# item_2022_Frontend_01.net
KiCad netlist of a schematic drawn in EAGLE
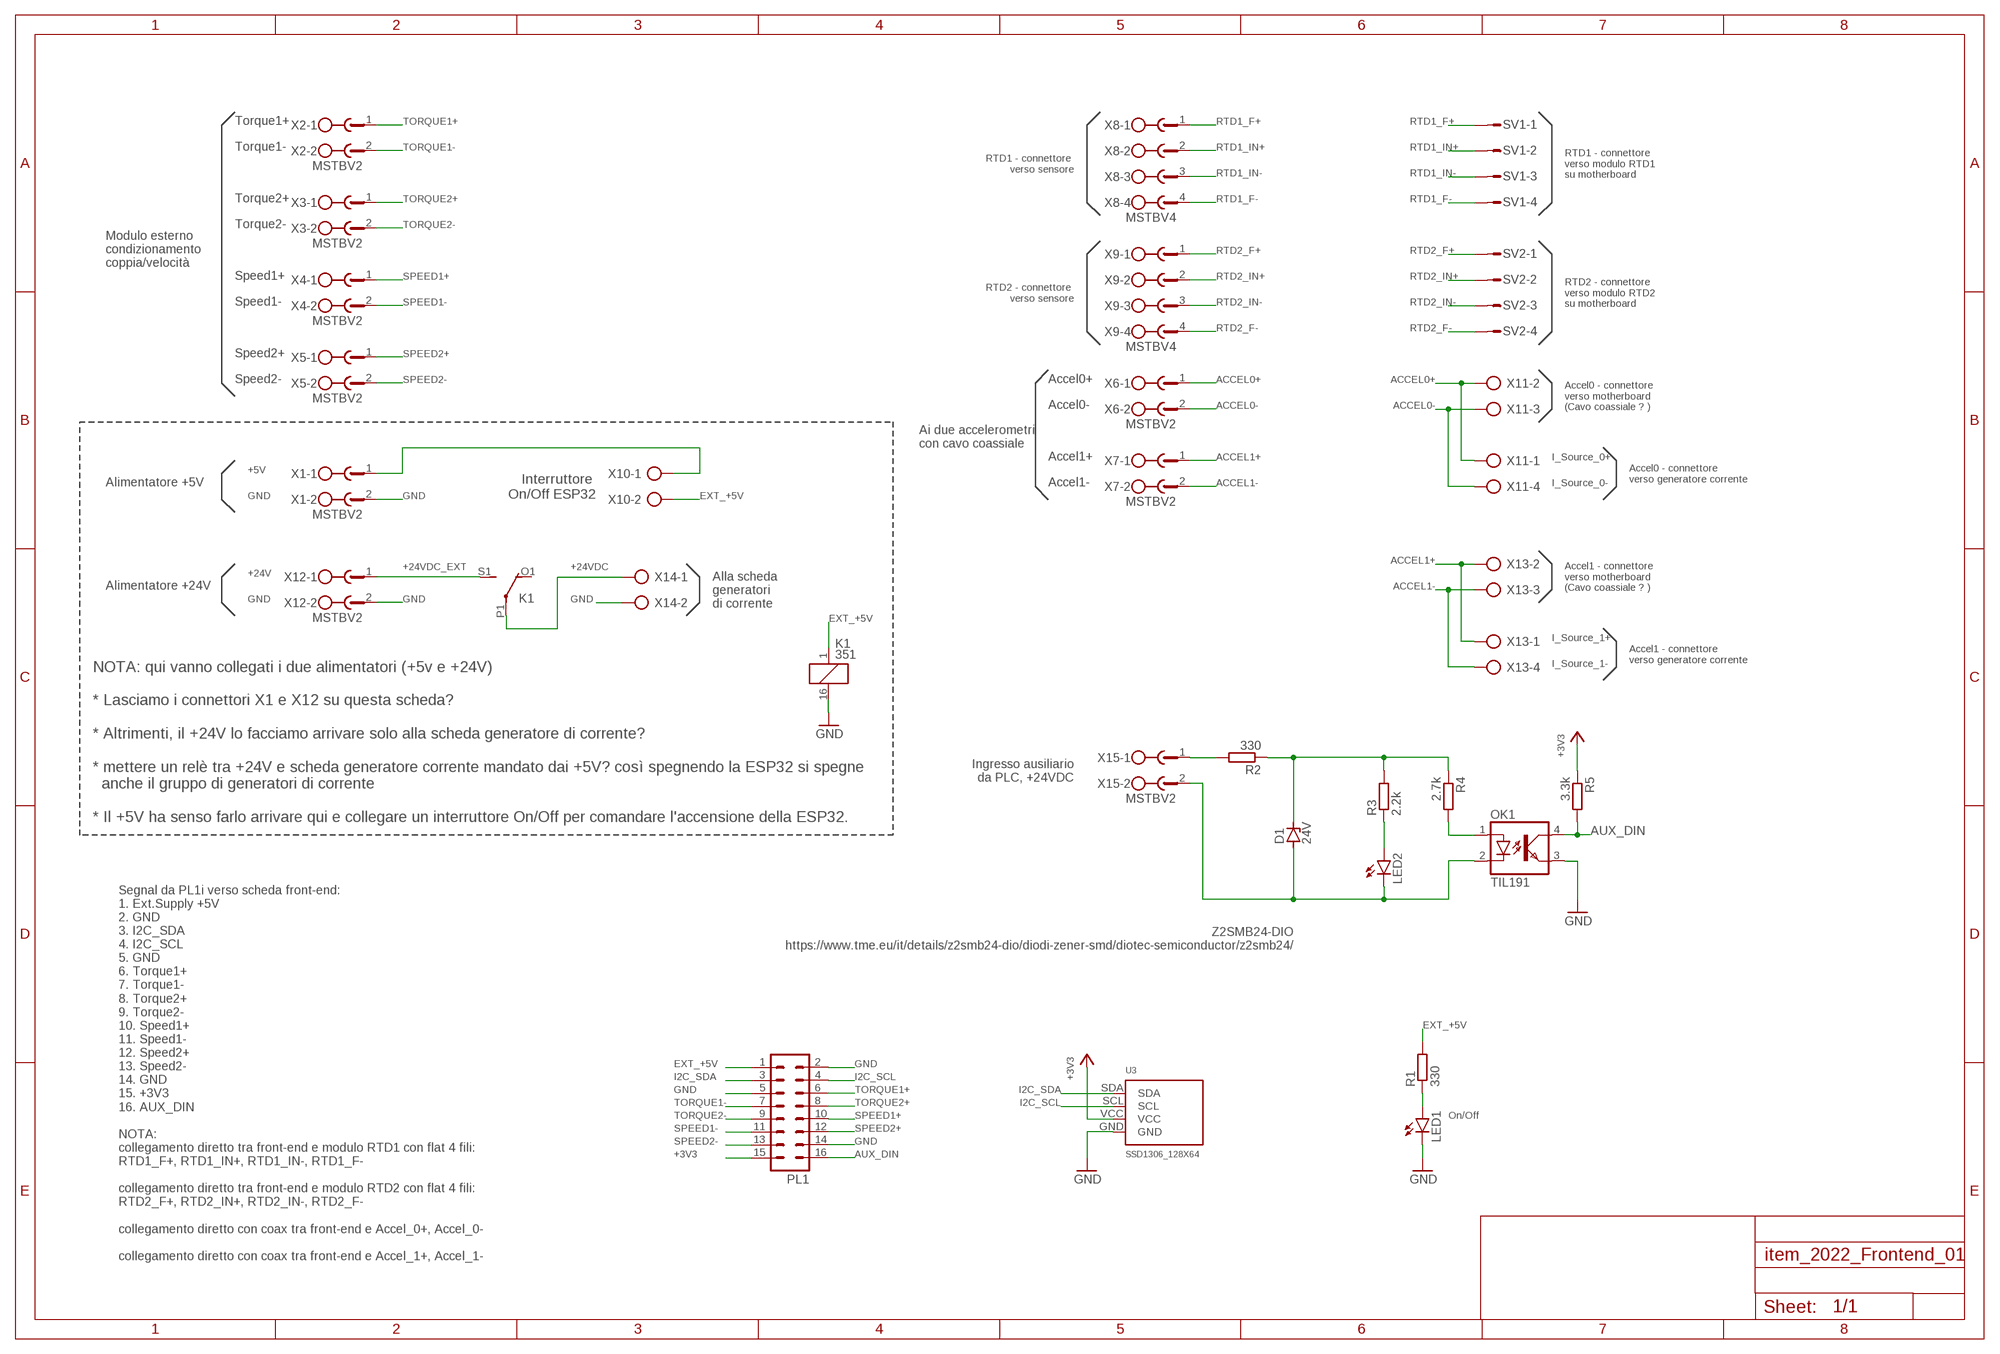
[diagram p0: schematic, sheet 1]

(export (version "E")
  (design (tool "Eeschema 10.0.6"))
  (components
    (comp (ref "D1")
      (value "24V")
      (footprint "eagle-import:SMB")
      (libsource (lib "eagle-import") (part "ZENER-DIODESMB"))
    )
    (comp (ref "K1")
      (value "351")
      (footprint "eagle-import:351")
      (libsource (lib "eagle-import") (part "351"))
    )
    (comp (ref "LED1")
      (value "LED5MM")
      (footprint "eagle-import:LED5MM")
      (libsource (lib "eagle-import") (part "LED5MM"))
    )
    (comp (ref "LED2")
      (value "LED5MM")
      (footprint "eagle-import:LED5MM")
      (libsource (lib "eagle-import") (part "LED5MM"))
    )
    (comp (ref "OK1")
      (value "TIL191")
      (footprint "eagle-import:DIL04")
      (libsource (lib "eagle-import") (part "TIL191"))
    )
    (comp (ref "PL1")
      (value "16V")
      (footprint "eagle-import:16V")
      (libsource (lib "eagle-import") (part "16V"))
    )
    (comp (ref "R1")
      (value "330")
      (footprint "eagle-import:R0805")
      (libsource (lib "eagle-import") (part "R-EU_R0805"))
    )
    (comp (ref "R2")
      (value "330")
      (footprint "eagle-import:R0805")
      (libsource (lib "eagle-import") (part "R-EU_R0805"))
    )
    (comp (ref "R3")
      (value "2.2k")
      (footprint "eagle-import:R0805")
      (libsource (lib "eagle-import") (part "R-EU_R0805"))
    )
    (comp (ref "R4")
      (value "2.7k")
      (footprint "eagle-import:R0805")
      (libsource (lib "eagle-import") (part "R-EU_R0805"))
    )
    (comp (ref "R5")
      (value "3.3k")
      (footprint "eagle-import:R0805")
      (libsource (lib "eagle-import") (part "R-EU_R0805"))
    )
    (comp (ref "SV1")
      (value "S04P")
      (footprint "eagle-import:S04P")
      (libsource (lib "eagle-import") (part "S04P"))
    )
    (comp (ref "SV2")
      (value "S04P")
      (footprint "eagle-import:S04P")
      (libsource (lib "eagle-import") (part "S04P"))
    )
    (comp (ref "U3")
      (value "SSD1306_128X64")
      (footprint "eagle-import:128X64")
      (libsource (lib "eagle-import") (part "SSD1306_128X64"))
    )
    (comp (ref "X1")
      (value "MSTBV2")
      (footprint "eagle-import:MSTBV2")
      (fields (field (name "MPN") "MSTBV 2,5/2-GF-5.08"))
      (libsource (lib "eagle-import") (part "MSTBV2"))
    )
    (comp (ref "X2")
      (value "MSTBV2")
      (footprint "eagle-import:MSTBV2")
      (fields (field (name "MPN") "MSTBV 2,5/2-GF-5.08"))
      (libsource (lib "eagle-import") (part "MSTBV2"))
    )
    (comp (ref "X3")
      (value "MSTBV2")
      (footprint "eagle-import:MSTBV2")
      (fields (field (name "MPN") "MSTBV 2,5/2-GF-5.08"))
      (libsource (lib "eagle-import") (part "MSTBV2"))
    )
    (comp (ref "X4")
      (value "MSTBV2")
      (footprint "eagle-import:MSTBV2")
      (fields (field (name "MPN") "MSTBV 2,5/2-GF-5.08"))
      (libsource (lib "eagle-import") (part "MSTBV2"))
    )
    (comp (ref "X5")
      (value "MSTBV2")
      (footprint "eagle-import:MSTBV2")
      (fields (field (name "MPN") "MSTBV 2,5/2-GF-5.08"))
      (libsource (lib "eagle-import") (part "MSTBV2"))
    )
    (comp (ref "X6")
      (value "MSTBV2")
      (footprint "eagle-import:MSTBV2")
      (fields (field (name "MPN") "MSTBV 2,5/2-GF-5.08"))
      (libsource (lib "eagle-import") (part "MSTBV2"))
    )
    (comp (ref "X7")
      (value "MSTBV2")
      (footprint "eagle-import:MSTBV2")
      (fields (field (name "MPN") "MSTBV 2,5/2-GF-5.08"))
      (libsource (lib "eagle-import") (part "MSTBV2"))
    )
    (comp (ref "X8")
      (value "MSTBV4")
      (footprint "eagle-import:MSTBV4")
      (fields (field (name "MPN") "MSTBV 2,5/4-GF-5.08"))
      (libsource (lib "eagle-import") (part "MSTBV4"))
    )
    (comp (ref "X9")
      (value "MSTBV4")
      (footprint "eagle-import:MSTBV4")
      (fields (field (name "MPN") "MSTBV 2,5/4-GF-5.08"))
      (libsource (lib "eagle-import") (part "MSTBV4"))
    )
    (comp (ref "X10")
      (value "AK500/2")
      (footprint "eagle-import:AK500_2")
      (libsource (lib "eagle-import") (part "AK500/2"))
    )
    (comp (ref "X11")
      (value "AK500/4")
      (footprint "eagle-import:AK500_4")
      (libsource (lib "eagle-import") (part "AK500/4"))
    )
    (comp (ref "X12")
      (value "MSTBV2")
      (footprint "eagle-import:MSTBV2")
      (fields (field (name "MPN") "MSTBV 2,5/2-GF-5.08"))
      (libsource (lib "eagle-import") (part "MSTBV2"))
    )
    (comp (ref "X13")
      (value "AK500/4")
      (footprint "eagle-import:AK500_4")
      (libsource (lib "eagle-import") (part "AK500/4"))
    )
    (comp (ref "X14")
      (value "AK500/2")
      (footprint "eagle-import:AK500_2")
      (libsource (lib "eagle-import") (part "AK500/2"))
    )
    (comp (ref "X15")
      (value "MSTBV2")
      (footprint "eagle-import:MSTBV2")
      (fields (field (name "MPN") "MSTBV 2,5/2-GF-5.08"))
      (libsource (lib "eagle-import") (part "MSTBV2"))
    )
  )
  (nets
    (net (code "1") (name "+3V3") (class "Default")
      (node (ref "PL1") (pin "15") (pinfunction "15_15") (pintype "passive"))
      (node (ref "R5") (pin "1") (pinfunction "1_1") (pintype "passive"))
      (node (ref "U3") (pin "VCC") (pinfunction "VCC_VCC") (pintype "power_in"))
    )
    (net (code "2") (name "/+24VDC") (class "Default")
      (node (ref "K1") (pin "P1") (pinfunction "P_P1") (pintype "passive"))
      (node (ref "X14") (pin "1") (pinfunction "KL_1") (pintype "passive"))
    )
    (net (code "3") (name "/+24VDC_EXT") (class "Default")
      (node (ref "K1") (pin "S1") (pinfunction "S_S1") (pintype "passive"))
      (node (ref "X12") (pin "1") (pinfunction "1_1") (pintype "passive"))
    )
    (net (code "4") (name "/ACCEL0+") (class "Default")
      (node (ref "X11") (pin "1") (pinfunction "KL_1") (pintype "passive"))
      (node (ref "X11") (pin "2") (pinfunction "KL_2") (pintype "passive"))
      (node (ref "X6") (pin "1") (pinfunction "1_1") (pintype "passive"))
    )
    (net (code "5") (name "/ACCEL0-") (class "Default")
      (node (ref "X11") (pin "3") (pinfunction "KL_3") (pintype "passive"))
      (node (ref "X11") (pin "4") (pinfunction "KL_4") (pintype "passive"))
      (node (ref "X6") (pin "2") (pinfunction "1_2") (pintype "passive"))
    )
    (net (code "6") (name "/ACCEL1+") (class "Default")
      (node (ref "X13") (pin "1") (pinfunction "KL_1") (pintype "passive"))
      (node (ref "X13") (pin "2") (pinfunction "KL_2") (pintype "passive"))
      (node (ref "X7") (pin "1") (pinfunction "1_1") (pintype "passive"))
    )
    (net (code "7") (name "/ACCEL1-") (class "Default")
      (node (ref "X13") (pin "3") (pinfunction "KL_3") (pintype "passive"))
      (node (ref "X13") (pin "4") (pinfunction "KL_4") (pintype "passive"))
      (node (ref "X7") (pin "2") (pinfunction "1_2") (pintype "passive"))
    )
    (net (code "8") (name "/AUX_DIN") (class "Default")
      (node (ref "OK1") (pin "4") (pinfunction "COL_4") (pintype "passive"))
      (node (ref "PL1") (pin "16") (pinfunction "16_16") (pintype "passive"))
      (node (ref "R5") (pin "2") (pinfunction "2_2") (pintype "passive"))
    )
    (net (code "9") (name "/EXT_+5V") (class "Default")
      (node (ref "K1") (pin "1") (pinfunction "1_1") (pintype "passive"))
      (node (ref "PL1") (pin "1") (pinfunction "1_1") (pintype "passive"))
      (node (ref "R1") (pin "2") (pinfunction "2_2") (pintype "passive"))
      (node (ref "X10") (pin "2") (pinfunction "KL_2") (pintype "passive"))
    )
    (net (code "10") (name "/I2C_SCL") (class "Default")
      (node (ref "PL1") (pin "4") (pinfunction "4_4") (pintype "passive"))
      (node (ref "U3") (pin "SCL") (pinfunction "SCL_SCL") (pintype "bidirectional"))
    )
    (net (code "11") (name "/I2C_SDA") (class "Default")
      (node (ref "PL1") (pin "3") (pinfunction "3_3") (pintype "passive"))
      (node (ref "U3") (pin "SDA") (pinfunction "SDA_SDA") (pintype "bidirectional"))
    )
    (net (code "12") (name "/RTD1_F+") (class "Default")
      (node (ref "SV1") (pin "1") (pinfunction "S_1") (pintype "passive"))
      (node (ref "X8") (pin "1") (pinfunction "1_1") (pintype "passive"))
    )
    (net (code "13") (name "/RTD1_F-") (class "Default")
      (node (ref "SV1") (pin "4") (pinfunction "S_4") (pintype "passive"))
      (node (ref "X8") (pin "4") (pinfunction "1_4") (pintype "passive"))
    )
    (net (code "14") (name "/RTD1_IN+") (class "Default")
      (node (ref "SV1") (pin "2") (pinfunction "S_2") (pintype "passive"))
      (node (ref "X8") (pin "2") (pinfunction "1_2") (pintype "passive"))
    )
    (net (code "15") (name "/RTD1_IN-") (class "Default")
      (node (ref "SV1") (pin "3") (pinfunction "S_3") (pintype "passive"))
      (node (ref "X8") (pin "3") (pinfunction "1_3") (pintype "passive"))
    )
    (net (code "16") (name "/RTD2_F+") (class "Default")
      (node (ref "SV2") (pin "1") (pinfunction "S_1") (pintype "passive"))
      (node (ref "X9") (pin "1") (pinfunction "1_1") (pintype "passive"))
    )
    (net (code "17") (name "/RTD2_F-") (class "Default")
      (node (ref "SV2") (pin "4") (pinfunction "S_4") (pintype "passive"))
      (node (ref "X9") (pin "4") (pinfunction "1_4") (pintype "passive"))
    )
    (net (code "18") (name "/RTD2_IN+") (class "Default")
      (node (ref "SV2") (pin "2") (pinfunction "S_2") (pintype "passive"))
      (node (ref "X9") (pin "2") (pinfunction "1_2") (pintype "passive"))
    )
    (net (code "19") (name "/RTD2_IN-") (class "Default")
      (node (ref "SV2") (pin "3") (pinfunction "S_3") (pintype "passive"))
      (node (ref "X9") (pin "3") (pinfunction "1_3") (pintype "passive"))
    )
    (net (code "20") (name "/SPEED1+") (class "Default")
      (node (ref "PL1") (pin "10") (pinfunction "10_10") (pintype "passive"))
      (node (ref "X4") (pin "1") (pinfunction "1_1") (pintype "passive"))
    )
    (net (code "21") (name "/SPEED1-") (class "Default")
      (node (ref "PL1") (pin "11") (pinfunction "11_11") (pintype "passive"))
      (node (ref "X4") (pin "2") (pinfunction "1_2") (pintype "passive"))
    )
    (net (code "22") (name "/SPEED2+") (class "Default")
      (node (ref "PL1") (pin "12") (pinfunction "12_12") (pintype "passive"))
      (node (ref "X5") (pin "1") (pinfunction "1_1") (pintype "passive"))
    )
    (net (code "23") (name "/SPEED2-") (class "Default")
      (node (ref "PL1") (pin "13") (pinfunction "13_13") (pintype "passive"))
      (node (ref "X5") (pin "2") (pinfunction "1_2") (pintype "passive"))
    )
    (net (code "24") (name "/TORQUE1+") (class "Default")
      (node (ref "PL1") (pin "6") (pinfunction "6_6") (pintype "passive"))
      (node (ref "X2") (pin "1") (pinfunction "1_1") (pintype "passive"))
    )
    (net (code "25") (name "/TORQUE1-") (class "Default")
      (node (ref "PL1") (pin "7") (pinfunction "7_7") (pintype "passive"))
      (node (ref "X2") (pin "2") (pinfunction "1_2") (pintype "passive"))
    )
    (net (code "26") (name "/TORQUE2+") (class "Default")
      (node (ref "PL1") (pin "8") (pinfunction "8_8") (pintype "passive"))
      (node (ref "X3") (pin "1") (pinfunction "1_1") (pintype "passive"))
    )
    (net (code "27") (name "/TORQUE2-") (class "Default")
      (node (ref "PL1") (pin "9") (pinfunction "9_9") (pintype "passive"))
      (node (ref "X3") (pin "2") (pinfunction "1_2") (pintype "passive"))
    )
    (net (code "28") (name "GND") (class "Default")
      (node (ref "K1") (pin "16") (pinfunction "2_16") (pintype "passive"))
      (node (ref "LED1") (pin "K") (pinfunction "C_K") (pintype "passive"))
      (node (ref "OK1") (pin "3") (pinfunction "EMIT_3") (pintype "passive"))
      (node (ref "PL1") (pin "14") (pinfunction "14_14") (pintype "passive"))
      (node (ref "PL1") (pin "2") (pinfunction "2_2") (pintype "passive"))
      (node (ref "PL1") (pin "5") (pinfunction "5_5") (pintype "passive"))
      (node (ref "U3") (pin "GND") (pinfunction "GND_GND") (pintype "power_in"))
      (node (ref "X1") (pin "2") (pinfunction "1_2") (pintype "passive"))
      (node (ref "X12") (pin "2") (pinfunction "1_2") (pintype "passive"))
      (node (ref "X14") (pin "2") (pinfunction "KL_2") (pintype "passive"))
    )
    (net (code "29") (name "Net-(D1-PadC)") (class "Default")
      (node (ref "D1") (pin "C") (pinfunction "C_C") (pintype "passive"))
      (node (ref "R2") (pin "1") (pinfunction "1_1") (pintype "passive"))
      (node (ref "R3") (pin "2") (pinfunction "2_2") (pintype "passive"))
      (node (ref "R4") (pin "1") (pinfunction "1_1") (pintype "passive"))
    )
    (net (code "30") (name "Net-(LED1-PadA)") (class "Default")
      (node (ref "LED1") (pin "A") (pinfunction "A_A") (pintype "passive"))
      (node (ref "R1") (pin "1") (pinfunction "1_1") (pintype "passive"))
    )
    (net (code "31") (name "Net-(LED2-C)") (class "Default")
      (node (ref "D1") (pin "A") (pinfunction "A_A") (pintype "passive"))
      (node (ref "LED2") (pin "K") (pinfunction "C_K") (pintype "passive"))
      (node (ref "OK1") (pin "2") (pinfunction "C_2") (pintype "passive"))
      (node (ref "X15") (pin "2") (pinfunction "1_2") (pintype "passive"))
    )
    (net (code "32") (name "Net-(LED2-PadA)") (class "Default")
      (node (ref "LED2") (pin "A") (pinfunction "A_A") (pintype "passive"))
      (node (ref "R3") (pin "1") (pinfunction "1_1") (pintype "passive"))
    )
    (net (code "33") (name "Net-(OK1-A)") (class "Default")
      (node (ref "OK1") (pin "1") (pinfunction "A_1") (pintype "passive"))
      (node (ref "R4") (pin "2") (pinfunction "2_2") (pintype "passive"))
    )
    (net (code "34") (name "Net-(R2-Pad2)") (class "Default")
      (node (ref "R2") (pin "2") (pinfunction "2_2") (pintype "passive"))
      (node (ref "X15") (pin "1") (pinfunction "1_1") (pintype "passive"))
    )
    (net (code "35") (name "Net-(X10A-KL)") (class "Default")
      (node (ref "X1") (pin "1") (pinfunction "1_1") (pintype "passive"))
      (node (ref "X10") (pin "1") (pinfunction "KL_1") (pintype "passive"))
    )
    (net (code "36") (name "unconnected-(K1B-O-PadO1)") (class "Default")
      (node (ref "K1") (pin "O1") (pinfunction "O_O1") (pintype "passive"))
    )
  )
)
